# RTD_1K_Wheatstone.net
KiCad netlist of a schematic drawn in Altium Designer
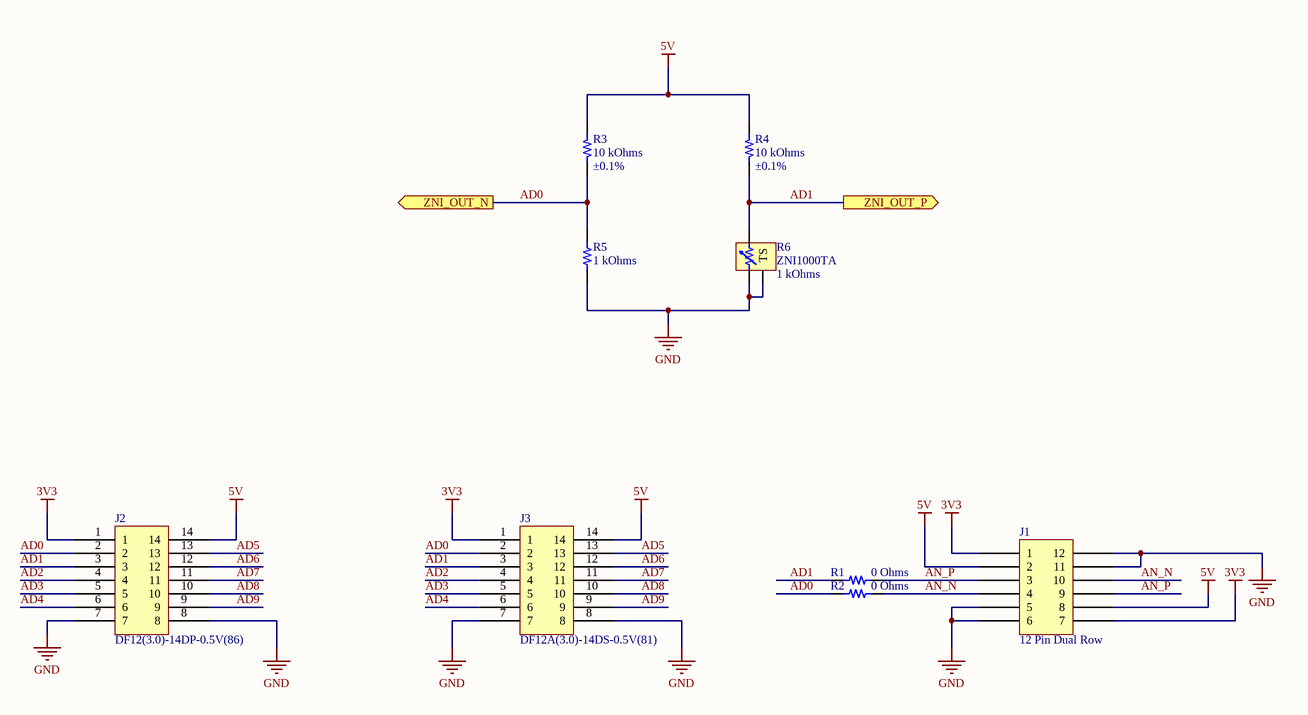
[diagram p0: RTD 1K Wheatstone.SchDoc]

(export (version "E")
  (design (tool "Eeschema 10.0.6"))
  (components
    (comp (ref "J1")
      (value "12 Pin Dual Row")
      (footprint "TE 5650118-3 Card Edge")
      (libsource (lib "CelestialUseful") (part "12 Pin Dual Row"))
    )
    (comp (ref "J2")
      (value "DF12(3.0)-14DP-0.5V(86)")
      (footprint "HIROSE DF12 3.0-14DP-0.5V 86")
      (description "CONN HDR 14POS SMD GOLD")
      (fields (field (name "MANUFACTURER") "Hirose Electric Co Ltd"))
      (libsource (lib "altiumlibrary.com") (part "14 Pin Dual Row"))
    )
    (comp (ref "J3")
      (value "DF12A(3.0)-14DS-0.5V(81)")
      (footprint "HIROSE DF12A 3.0-14DS-0.5V 81")
      (description "CONN RCPT 14POS SMD GOLD")
      (fields (field (name "MANUFACTURER") "Hirose Electric Co Ltd"))
      (libsource (lib "altiumlibrary.com") (part "14 Pin Dual Row"))
    )
    (comp (ref "R1")
      (value "0 Ohms")
      (footprint "RES 0603_1608")
      (description "RES SMD 0 OHM JUMPER 1/10W 0603")
      (fields
        (field (name "PART NUMBER") "ERJ-3GEY0R00V")
        (field (name "MANUFACTURER") "Panasonic Electronic Components")
      )
      (libsource (lib "altiumlibrary.com") (part "Resistor"))
    )
    (comp (ref "R2")
      (value "0 Ohms")
      (footprint "RES 0603_1608")
      (description "RES SMD 0 OHM JUMPER 1/10W 0603")
      (fields
        (field (name "PART NUMBER") "ERJ-3GEY0R00V")
        (field (name "MANUFACTURER") "Panasonic Electronic Components")
      )
      (libsource (lib "altiumlibrary.com") (part "Resistor"))
    )
    (comp (ref "R3")
      (value "10 kOhms")
      (footprint "RES 0603_1608")
      (description "RES SMD 10K OHM 0.1% 1/10W 0603")
      (fields
        (field (name "PART NUMBER") "ERA-3AEB103V")
        (field (name "MANUFACTURER") "Panasonic Electronic Components")
        (field (name "TOLERANCE") "±0.1%")
      )
      (libsource (lib "altiumlibrary.com") (part "Resistor"))
    )
    (comp (ref "R4")
      (value "10 kOhms")
      (footprint "RES 0603_1608")
      (description "RES SMD 10K OHM 0.1% 1/10W 0603")
      (fields
        (field (name "PART NUMBER") "ERA-3AEB103V")
        (field (name "MANUFACTURER") "Panasonic Electronic Components")
        (field (name "TOLERANCE") "±0.1%")
      )
      (libsource (lib "altiumlibrary.com") (part "Resistor"))
    )
    (comp (ref "R5")
      (value "1 kOhms")
      (footprint "RES 0603_1608")
      (description "RES SMD 1K OHM 0.1% 1/5W 0603")
      (fields
        (field (name "PART NUMBER") "ERJ-PB3B1001V")
        (field (name "MANUFACTURER") "Panasonic Electronic Components")
      )
      (libsource (lib "altiumlibrary.com") (part "Resistor"))
    )
    (comp (ref "R6")
      (value "ZNI1000TA")
      (footprint "DIODES SOT-23-3")
      (description "SENSOR RTD 1KOHM 5% TO236-3")
      (fields (field (name "MANUFACTURER") "Diodes Incorporated") (field (name "RESISTANCE @ 0°C") "1 kOhms"))
      (libsource (lib "altiumlibrary.com") (part "DIODES INC ZNI1000"))
    )
  )
  (nets
    (net (code "1") (name "/AD0") (class "Default")
      (node (ref "J2") (pin "2") (pinfunction "2_2") (pintype "passive"))
      (node (ref "J3") (pin "2") (pinfunction "2_2") (pintype "passive"))
      (node (ref "R2") (pin "1") (pinfunction "1_1") (pintype "passive"))
      (node (ref "R3") (pin "1") (pinfunction "1_1") (pintype "passive"))
      (node (ref "R5") (pin "2") (pinfunction "2_2") (pintype "passive"))
    )
    (net (code "2") (name "/AD1") (class "Default")
      (node (ref "J2") (pin "3") (pinfunction "3_3") (pintype "passive"))
      (node (ref "J3") (pin "3") (pinfunction "3_3") (pintype "passive"))
      (node (ref "R1") (pin "1") (pinfunction "1_1") (pintype "passive"))
      (node (ref "R4") (pin "1") (pinfunction "1_1") (pintype "passive"))
      (node (ref "R6") (pin "2") (pinfunction "2_2") (pintype "passive"))
    )
    (net (code "3") (name "/AD2") (class "Default")
      (node (ref "J2") (pin "4") (pinfunction "4_4") (pintype "passive"))
      (node (ref "J3") (pin "4") (pinfunction "4_4") (pintype "passive"))
    )
    (net (code "4") (name "/AD3") (class "Default")
      (node (ref "J2") (pin "5") (pinfunction "5_5") (pintype "passive"))
      (node (ref "J3") (pin "5") (pinfunction "5_5") (pintype "passive"))
    )
    (net (code "5") (name "/AD4") (class "Default")
      (node (ref "J2") (pin "6") (pinfunction "6_6") (pintype "passive"))
      (node (ref "J3") (pin "6") (pinfunction "6_6") (pintype "passive"))
    )
    (net (code "6") (name "/AD5") (class "Default")
      (node (ref "J2") (pin "13") (pinfunction "13_13") (pintype "passive"))
      (node (ref "J3") (pin "13") (pinfunction "13_13") (pintype "passive"))
    )
    (net (code "7") (name "/AD6") (class "Default")
      (node (ref "J2") (pin "12") (pinfunction "12_12") (pintype "passive"))
      (node (ref "J3") (pin "12") (pinfunction "12_12") (pintype "passive"))
    )
    (net (code "8") (name "/AD7") (class "Default")
      (node (ref "J2") (pin "11") (pinfunction "11_11") (pintype "passive"))
      (node (ref "J3") (pin "11") (pinfunction "11_11") (pintype "passive"))
    )
    (net (code "9") (name "/AD8") (class "Default")
      (node (ref "J2") (pin "10") (pinfunction "10_10") (pintype "passive"))
      (node (ref "J3") (pin "10") (pinfunction "10_10") (pintype "passive"))
    )
    (net (code "10") (name "/AD9") (class "Default")
      (node (ref "J2") (pin "9") (pinfunction "9_9") (pintype "passive"))
      (node (ref "J3") (pin "9") (pinfunction "9_9") (pintype "passive"))
    )
    (net (code "11") (name "/AN_N") (class "Default")
      (node (ref "J1") (pin "10") (pinfunction "10_10") (pintype "passive"))
      (node (ref "J1") (pin "4") (pinfunction "4_4") (pintype "passive"))
      (node (ref "R2") (pin "2") (pinfunction "2_2") (pintype "passive"))
    )
    (net (code "12") (name "/AN_P") (class "Default")
      (node (ref "J1") (pin "3") (pinfunction "3_3") (pintype "passive"))
      (node (ref "J1") (pin "9") (pinfunction "9_9") (pintype "passive"))
      (node (ref "R1") (pin "2") (pinfunction "2_2") (pintype "passive"))
    )
    (net (code "13") (name "3V3") (class "Default")
      (node (ref "J1") (pin "1") (pinfunction "1_1") (pintype "passive"))
      (node (ref "J1") (pin "7") (pinfunction "7_7") (pintype "passive"))
      (node (ref "J2") (pin "1") (pinfunction "1_1") (pintype "passive"))
      (node (ref "J3") (pin "1") (pinfunction "1_1") (pintype "passive"))
    )
    (net (code "14") (name "5V") (class "Default")
      (node (ref "J1") (pin "2") (pinfunction "2_2") (pintype "passive"))
      (node (ref "J1") (pin "8") (pinfunction "8_8") (pintype "passive"))
      (node (ref "J2") (pin "14") (pinfunction "14_14") (pintype "passive"))
      (node (ref "J3") (pin "14") (pinfunction "14_14") (pintype "passive"))
      (node (ref "R3") (pin "2") (pinfunction "2_2") (pintype "passive"))
      (node (ref "R4") (pin "2") (pinfunction "2_2") (pintype "passive"))
    )
    (net (code "15") (name "GND") (class "Default")
      (node (ref "J1") (pin "11") (pinfunction "11_11") (pintype "passive"))
      (node (ref "J1") (pin "12") (pinfunction "12_12") (pintype "passive"))
      (node (ref "J1") (pin "5") (pinfunction "5_5") (pintype "passive"))
      (node (ref "J1") (pin "6") (pinfunction "6_6") (pintype "passive"))
      (node (ref "J2") (pin "7") (pinfunction "7_7") (pintype "passive"))
      (node (ref "J2") (pin "8") (pinfunction "8_8") (pintype "passive"))
      (node (ref "J3") (pin "7") (pinfunction "7_7") (pintype "passive"))
      (node (ref "J3") (pin "8") (pinfunction "8_8") (pintype "passive"))
      (node (ref "R5") (pin "1") (pinfunction "1_1") (pintype "passive"))
      (node (ref "R6") (pin "1") (pinfunction "1_1") (pintype "passive"))
      (node (ref "R6") (pin "3") (pinfunction "TS_3") (pintype "passive"))
    )
  )
)
